# 5V_LS.net
KiCad netlist of a schematic drawn in Altium Designer
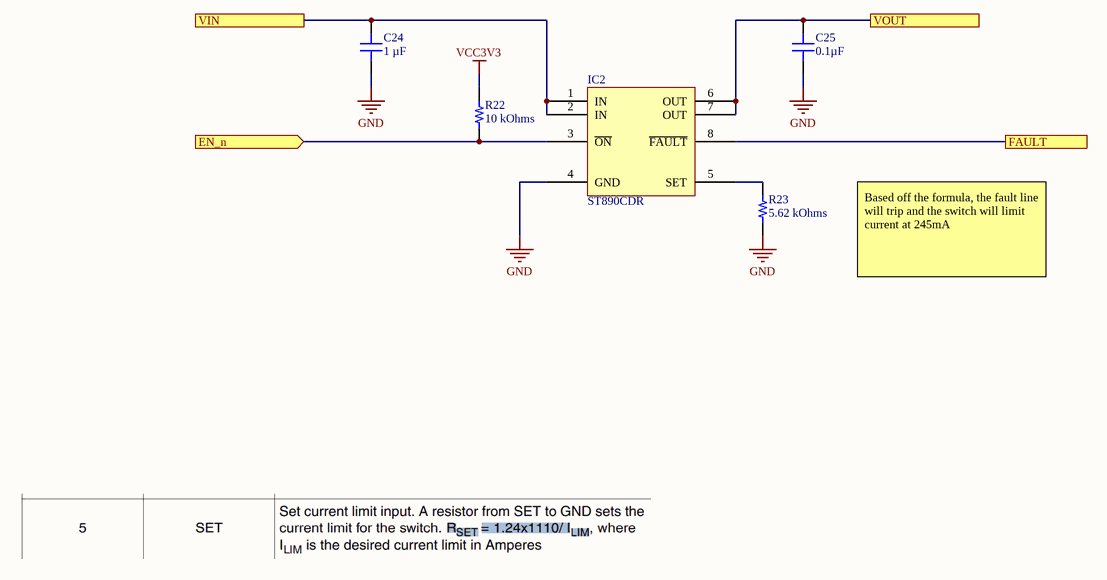
[diagram p0: 5V_LS.SchDoc]

(export (version "E")
  (design (tool "Eeschema 10.0.6"))
  (components
    (comp (ref "C24")
      (value "1 µF")
      (footprint "CAP 0402_1005")
      (description "CAP CER 1UF 10V X7S 0402")
      (fields
        (field (name "PART NUMBER") "GRM155C71A105KE11D")
        (field (name "MANUFACTURER") "Murata Electronics")
      )
      (libsource (lib "Celestial") (part "Capacitor"))
    )
    (comp (ref "C25")
      (value "0.1µF")
      (footprint "CAP 0402_1005")
      (description "CAP CER 0.1UF 10V X7R 0402")
      (fields (field (name "PART NUMBER") "0402ZC104KAT2A") (field (name "MANUFACTURER") "AVX Corporation"))
      (libsource (lib "Celestial") (part "Capacitor"))
    )
    (comp (ref "IC2")
      (value "ST890CDR")
      (footprint "ST SOIC-8N")
      (description "IC PWR SWITCH P-CHANNEL 1:1 8SO")
      (fields (field (name "MANUFACTURER") "STMicroelectronics"))
      (libsource (lib "Celestial") (part "ST ST890CDR"))
    )
    (comp (ref "R22")
      (value "10 kOhms")
      (footprint "RES 0402_1005")
      (description "RES 10K OHM 0.1% 1/10W 0402")
      (fields
        (field (name "PART NUMBER") "RP73PF1E10KBTD")
        (field (name "MANUFACTURER") "TE Connectivity Passive Product")
      )
      (libsource (lib "Celestial") (part "Resistor"))
    )
    (comp (ref "R23")
      (value "5.62 kOhms")
      (footprint "RES 0402_1005")
      (description "RES 5.62K OHM 0.1% 1/10W 0402")
      (fields
        (field (name "PART NUMBER") "RP73PF1E5K62BTD")
        (field (name "MANUFACTURER") "TE Connectivity Passive Product")
      )
      (libsource (lib "Celestial") (part "Resistor"))
    )
  )
  (nets
    (net (code "1") (name "/EN_n") (class "Default")
      (node (ref "IC2") (pin "3") (pinfunction "~{ON}_3") (pintype "passive"))
      (node (ref "R22") (pin "1") (pinfunction "1_1") (pintype "passive"))
    )
    (net (code "2") (name "/FAULT") (class "Default")
      (node (ref "IC2") (pin "8") (pinfunction "~{FAULT}_8") (pintype "passive"))
    )
    (net (code "3") (name "/VIN") (class "Default")
      (node (ref "C24") (pin "2") (pinfunction "2_2") (pintype "passive"))
      (node (ref "IC2") (pin "1") (pinfunction "IN_1") (pintype "passive"))
      (node (ref "IC2") (pin "2") (pinfunction "IN_2") (pintype "passive"))
    )
    (net (code "4") (name "/VOUT") (class "Default")
      (node (ref "C25") (pin "2") (pinfunction "2_2") (pintype "passive"))
      (node (ref "IC2") (pin "6") (pinfunction "OUT_6") (pintype "passive"))
      (node (ref "IC2") (pin "7") (pinfunction "OUT_7") (pintype "passive"))
    )
    (net (code "5") (name "GND") (class "Default")
      (node (ref "C24") (pin "1") (pinfunction "1_1") (pintype "passive"))
      (node (ref "C25") (pin "1") (pinfunction "1_1") (pintype "passive"))
      (node (ref "IC2") (pin "4") (pinfunction "GND_4") (pintype "passive"))
      (node (ref "R23") (pin "1") (pinfunction "1_1") (pintype "passive"))
    )
    (net (code "6") (name "Net-(IC2-SET)") (class "Default")
      (node (ref "IC2") (pin "5") (pinfunction "SET_5") (pintype "passive"))
      (node (ref "R23") (pin "2") (pinfunction "2_2") (pintype "passive"))
    )
    (net (code "7") (name "VCC3V3") (class "Default")
      (node (ref "R22") (pin "2") (pinfunction "2_2") (pintype "passive"))
    )
  )
)
